# USB_OTG_FS.net
KiCad netlist of a schematic drawn in Altium Designer
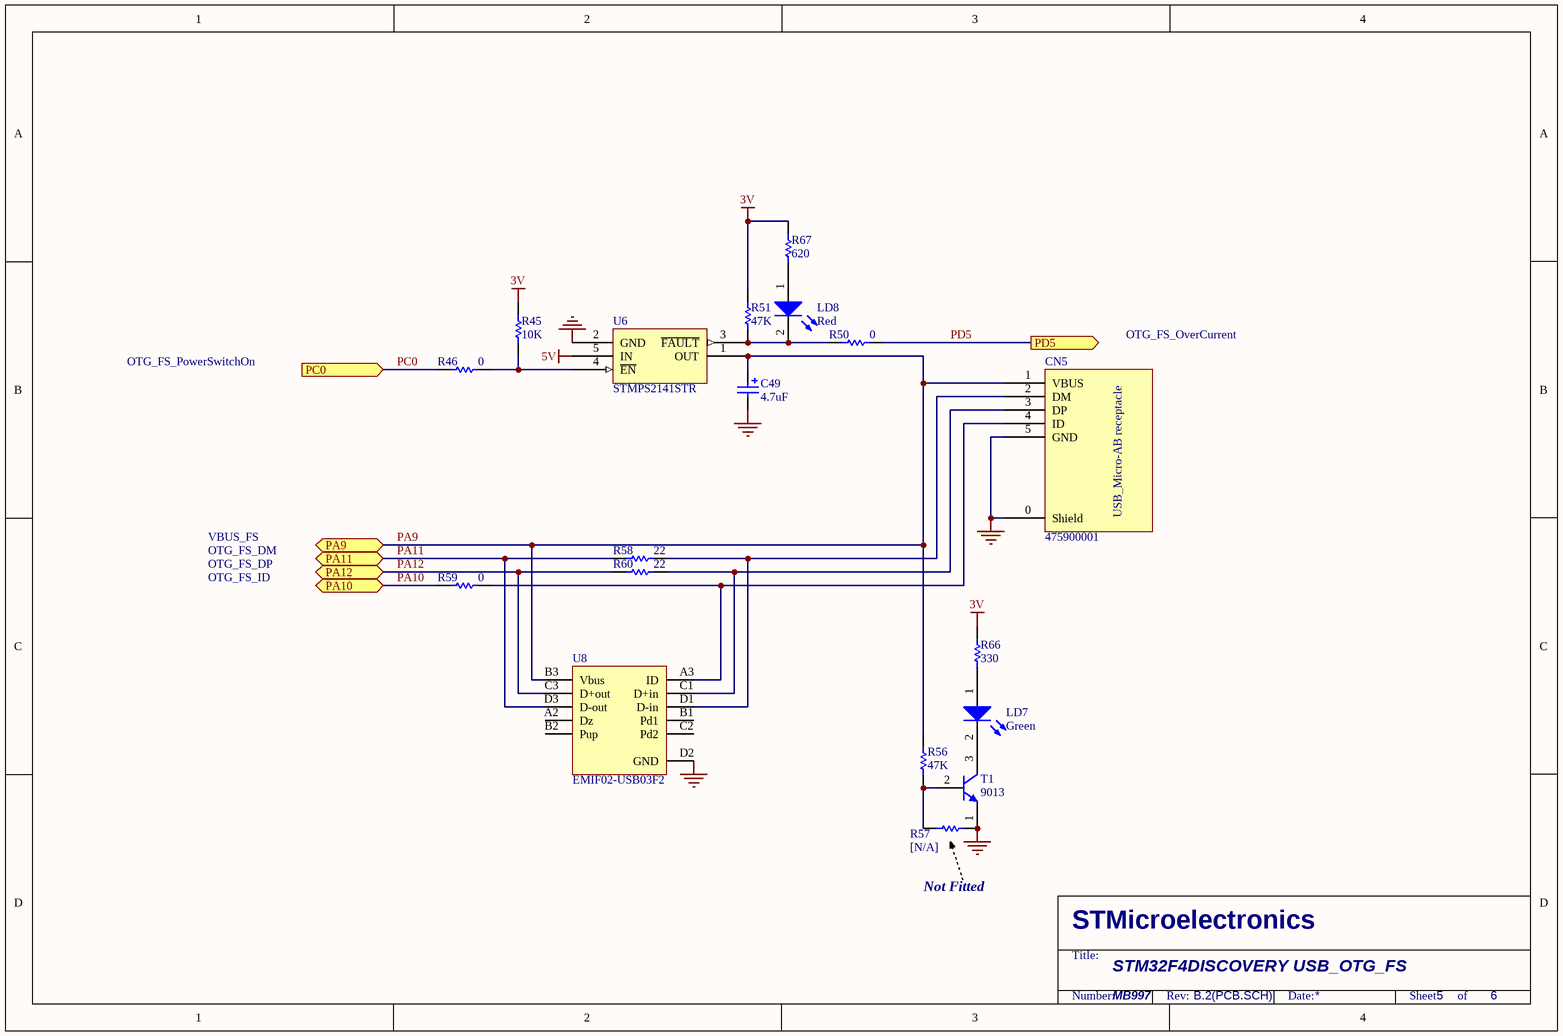
[diagram p0: USB_OTG_FS.SchDoc]

(export (version "E")
  (design (tool "Eeschema 10.0.6"))
  (components
    (comp (ref "C49")
      (value "4.7uF")
      (footprint "TAN-A")
      (description "Polarized Capacitor (Radial)")
      (fields (field (name "PUBLISHER") "Altium Limited"))
      (libsource (lib "Miscellaneous Devices") (part "Cap Pol1"))
    )
    (comp (ref "CN5")
      (value "475900001")
      (footprint "USB-MICRO-AB")
      (libsource (lib "MB786") (part "475900001"))
    )
    (comp (ref "LD7")
      (value "Green")
      (footprint "0603D")
      (description "Typical RED, GREEN, YELLOW, AMBER GaAs LED")
      (fields (field (name "PUBLISHER") "Altium Limited"))
      (libsource (lib "Miscellaneous Devices") (part "LED2"))
    )
    (comp (ref "LD8")
      (value "Red")
      (footprint "0603D")
      (description "Typical RED, GREEN, YELLOW, AMBER GaAs LED")
      (fields (field (name "PUBLISHER") "Altium Limited"))
      (libsource (lib "Miscellaneous Devices") (part "LED2"))
    )
    (comp (ref "R45")
      (value "10K")
      (footprint "0402R")
      (description "Resistor")
      (fields (field (name "PUBLISHER") "Altium Limited"))
      (libsource (lib "Miscellaneous Devices") (part "res1"))
    )
    (comp (ref "R46")
      (value "0")
      (footprint "0603R")
      (description "Resistor")
      (fields (field (name "PUBLISHER") "Altium Limited"))
      (libsource (lib "Miscellaneous Devices") (part "Res1"))
    )
    (comp (ref "R50")
      (value "0")
      (footprint "0603R")
      (description "Resistor")
      (fields (field (name "PUBLISHER") "Altium Limited"))
      (libsource (lib "Miscellaneous Devices") (part "Res1"))
    )
    (comp (ref "R51")
      (value "47K")
      (footprint "0402R")
      (description "Resistor")
      (fields (field (name "PUBLISHER") "Altium Limited"))
      (libsource (lib "Miscellaneous Devices") (part "res1"))
    )
    (comp (ref "R56")
      (value "47K")
      (footprint "0402R")
      (description "Resistor")
      (fields (field (name "PUBLISHER") "Altium Limited"))
      (libsource (lib "Miscellaneous Devices") (part "res1"))
    )
    (comp (ref "R57")
      (value "[N/A]")
      (footprint "0603R")
      (description "Resistor")
      (fields (field (name "PUBLISHER") "Altium Limited"))
      (libsource (lib "Miscellaneous Devices") (part "res1"))
    )
    (comp (ref "R58")
      (value "22")
      (footprint "0603R")
      (description "Resistor")
      (fields (field (name "PUBLISHER") "Altium Limited"))
      (libsource (lib "Miscellaneous Devices") (part "Res1"))
    )
    (comp (ref "R59")
      (value "0")
      (footprint "0603R")
      (description "Resistor")
      (fields (field (name "PUBLISHER") "Altium Limited"))
      (libsource (lib "Miscellaneous Devices") (part "Res1"))
    )
    (comp (ref "R60")
      (value "22")
      (footprint "0603R")
      (description "Resistor")
      (fields (field (name "PUBLISHER") "Altium Limited"))
      (libsource (lib "Miscellaneous Devices") (part "Res1"))
    )
    (comp (ref "R66")
      (value "330")
      (footprint "0603R")
      (description "Resistor")
      (fields (field (name "PUBLISHER") "Altium Limited"))
      (libsource (lib "Miscellaneous Devices") (part "res1"))
    )
    (comp (ref "R67")
      (value "620")
      (footprint "0603R")
      (description "Resistor")
      (fields (field (name "PUBLISHER") "Altium Limited"))
      (libsource (lib "Miscellaneous Devices") (part "Res1"))
    )
    (comp (ref "T1")
      (value "9013")
      (footprint "SOT-23")
      (description "NPN Bipolar Transistor")
      (fields (field (name "PUBLISHER") "Altium Limited"))
      (libsource (lib "Miscellaneous Devices") (part "NPN"))
    )
    (comp (ref "U6")
      (value "STMPS2141STR")
      (footprint "SOT23-5L")
      (description "Enhanced single channel power switches")
      (libsource (lib "MB997") (part "STMPS2141STR"))
    )
    (comp (ref "U8")
      (value "EMIF02-USB03F2")
      (footprint "Flip Chip")
      (description "2-line IPAD, EMI filter including ESD protection")
      (libsource (lib "MB997") (part "EMIF02-USB03F2"))
    )
  )
  (nets
    (net (code "1") (name "/PA9") (class "Default")
      (node (ref "C49") (pin "1") (pinfunction "1_1") (pintype "passive"))
      (node (ref "CN5") (pin "1") (pinfunction "VBUS_1") (pintype "passive"))
      (node (ref "R56") (pin "2") (pinfunction "2_2") (pintype "passive"))
      (node (ref "U6") (pin "1") (pinfunction "OUT_1") (pintype "passive"))
      (node (ref "U8") (pin "B3") (pinfunction "Vbus_B3") (pintype "passive"))
    )
    (net (code "2") (name "/PA10") (class "Default")
      (node (ref "R59") (pin "2") (pinfunction "2_2") (pintype "passive"))
    )
    (net (code "3") (name "/PA11") (class "Default")
      (node (ref "R58") (pin "2") (pinfunction "2_2") (pintype "passive"))
      (node (ref "U8") (pin "D3") (pinfunction "D-out_D3") (pintype "passive"))
    )
    (net (code "4") (name "/PA12") (class "Default")
      (node (ref "R60") (pin "2") (pinfunction "2_2") (pintype "passive"))
      (node (ref "U8") (pin "C3") (pinfunction "D+out_C3") (pintype "passive"))
    )
    (net (code "5") (name "/PC0") (class "Default")
      (node (ref "R46") (pin "2") (pinfunction "2_2") (pintype "passive"))
    )
    (net (code "6") (name "/PD5") (class "Default")
      (node (ref "R50") (pin "1") (pinfunction "1_1") (pintype "passive"))
    )
    (net (code "7") (name "3V") (class "Default")
      (node (ref "R45") (pin "1") (pinfunction "1_1") (pintype "passive"))
      (node (ref "R51") (pin "1") (pinfunction "1_1") (pintype "passive"))
      (node (ref "R66") (pin "2") (pinfunction "2_2") (pintype "passive"))
      (node (ref "R67") (pin "2") (pinfunction "2_2") (pintype "passive"))
    )
    (net (code "8") (name "5V") (class "Default")
      (node (ref "U6") (pin "5") (pinfunction "IN_5") (pintype "passive"))
    )
    (net (code "9") (name "GND") (class "Default")
      (node (ref "C49") (pin "2") (pinfunction "2_2") (pintype "passive"))
      (node (ref "CN5") (pin "0") (pinfunction "Shield_0") (pintype "passive"))
      (node (ref "CN5") (pin "5") (pinfunction "GND_5") (pintype "passive"))
      (node (ref "R57") (pin "1") (pinfunction "1_1") (pintype "passive"))
      (node (ref "T1") (pin "1") (pinfunction "E_1") (pintype "passive"))
      (node (ref "U6") (pin "2") (pinfunction "GND_2") (pintype "passive"))
      (node (ref "U8") (pin "D2") (pinfunction "GND_D2") (pintype "passive"))
    )
    (net (code "10") (name "Net-(CN5-DM)") (class "Default")
      (node (ref "CN5") (pin "2") (pinfunction "DM_2") (pintype "passive"))
      (node (ref "R58") (pin "1") (pinfunction "1_1") (pintype "passive"))
      (node (ref "U8") (pin "D1") (pinfunction "D-in_D1") (pintype "passive"))
    )
    (net (code "11") (name "Net-(CN5-DP)") (class "Default")
      (node (ref "CN5") (pin "3") (pinfunction "DP_3") (pintype "passive"))
      (node (ref "R60") (pin "1") (pinfunction "1_1") (pintype "passive"))
      (node (ref "U8") (pin "C1") (pinfunction "D+in_C1") (pintype "passive"))
    )
    (net (code "12") (name "Net-(CN5-ID)") (class "Default")
      (node (ref "CN5") (pin "4") (pinfunction "ID_4") (pintype "passive"))
      (node (ref "R59") (pin "1") (pinfunction "1_1") (pintype "passive"))
      (node (ref "U8") (pin "A3") (pinfunction "ID_A3") (pintype "passive"))
    )
    (net (code "13") (name "Net-(LD7-A)") (class "Default")
      (node (ref "LD7") (pin "1") (pinfunction "A_1") (pintype "passive"))
      (node (ref "R66") (pin "1") (pinfunction "1_1") (pintype "passive"))
    )
    (net (code "14") (name "Net-(LD7-K)") (class "Default")
      (node (ref "LD7") (pin "2") (pinfunction "K_2") (pintype "passive"))
      (node (ref "T1") (pin "3") (pinfunction "C_3") (pintype "passive"))
    )
    (net (code "15") (name "Net-(LD8-A)") (class "Default")
      (node (ref "LD8") (pin "1") (pinfunction "A_1") (pintype "passive"))
      (node (ref "R67") (pin "1") (pinfunction "1_1") (pintype "passive"))
    )
    (net (code "16") (name "Net-(LD8-K)") (class "Default")
      (node (ref "LD8") (pin "2") (pinfunction "K_2") (pintype "passive"))
      (node (ref "R50") (pin "2") (pinfunction "2_2") (pintype "passive"))
      (node (ref "R51") (pin "2") (pinfunction "2_2") (pintype "passive"))
      (node (ref "U6") (pin "3") (pinfunction "~{FAULT}_3") (pintype "output"))
    )
    (net (code "17") (name "Net-(T1-B)") (class "Default")
      (node (ref "R56") (pin "1") (pinfunction "1_1") (pintype "passive"))
      (node (ref "R57") (pin "2") (pinfunction "2_2") (pintype "passive"))
      (node (ref "T1") (pin "2") (pinfunction "B_2") (pintype "passive"))
    )
    (net (code "18") (name "Net-(U6-~{EN})") (class "Default")
      (node (ref "R45") (pin "2") (pinfunction "2_2") (pintype "passive"))
      (node (ref "R46") (pin "1") (pinfunction "1_1") (pintype "passive"))
      (node (ref "U6") (pin "4") (pinfunction "~{EN}_4") (pintype "input"))
    )
    (net (code "19") (name "unconnected-(U8-Dz-PadA2)") (class "Default")
      (node (ref "U8") (pin "A2") (pinfunction "Dz_A2") (pintype "passive"))
    )
    (net (code "20") (name "unconnected-(U8-Pd1-PadB1)") (class "Default")
      (node (ref "U8") (pin "B1") (pinfunction "Pd1_B1") (pintype "passive"))
    )
    (net (code "21") (name "unconnected-(U8-Pd2-PadC2)") (class "Default")
      (node (ref "U8") (pin "C2") (pinfunction "Pd2_C2") (pintype "passive"))
    )
    (net (code "22") (name "unconnected-(U8-Pup-PadB2)") (class "Default")
      (node (ref "U8") (pin "B2") (pinfunction "Pup_B2") (pintype "passive"))
    )
  )
)
